# breadBUG_v1.net
KiCad netlist of a schematic drawn in EAGLE
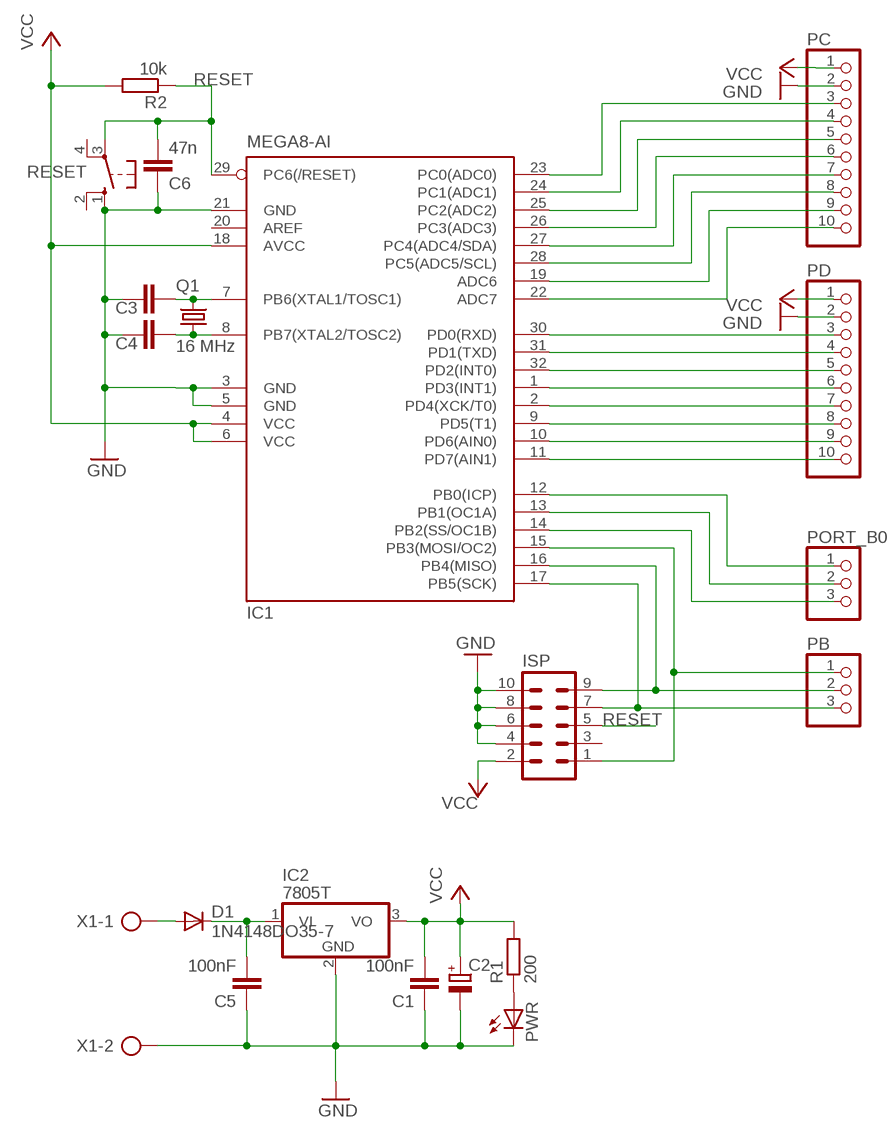
[diagram p0: schematic, sheet 1]

(export (version "E")
  (design (tool "Eeschema 10.0.6"))
  (components
    (comp (ref "C1")
      (value "100nF")
      (footprint "eagle-import:C2.5-2")
      (libsource (lib "eagle-import") (part "C2.5/2"))
    )
    (comp (ref "C2")
      (value "CPOL-EUE2.5-6")
      (footprint "eagle-import:E2,5-6")
      (libsource (lib "eagle-import") (part "CPOL-EUE2.5-6"))
    )
    (comp (ref "C3")
      (value "C-EU025-025X050")
      (footprint "eagle-import:C025-025X050")
      (libsource (lib "eagle-import") (part "C-EU025-025X050"))
    )
    (comp (ref "C4")
      (value "C-EU025-025X050")
      (footprint "eagle-import:C025-025X050")
      (libsource (lib "eagle-import") (part "C-EU025-025X050"))
    )
    (comp (ref "C5")
      (value "100nF")
      (footprint "eagle-import:C2.5-2")
      (libsource (lib "eagle-import") (part "C2.5/2"))
    )
    (comp (ref "C6")
      (value "47n")
      (footprint "eagle-import:C025-025X050")
      (libsource (lib "eagle-import") (part "C-EU025-025X050"))
    )
    (comp (ref "D1")
      (value "1N4148DO35-7")
      (footprint "eagle-import:DO35-7")
      (libsource (lib "eagle-import") (part "1N4148DO35-7"))
    )
    (comp (ref "IC1")
      (value "MEGA8-AI")
      (footprint "eagle-import:TQFP32-08")
      (fields (field (name "MPN") "ATMEGA8-16AU"))
      (libsource (lib "eagle-import") (part "MEGA8-AI"))
    )
    (comp (ref "IC2")
      (value "7805T")
      (footprint "eagle-import:TO220H")
      (libsource (lib "eagle-import") (part "78T05"))
    )
    (comp (ref "ISP")
      (value "MA05-2")
      (footprint "eagle-import:MA05-2")
      (libsource (lib "eagle-import") (part "MA05-2"))
    )
    (comp (ref "PB")
      (value "PINHD-1X3")
      (footprint "eagle-import:1X03")
      (libsource (lib "eagle-import") (part "PINHD-1X3"))
    )
    (comp (ref "PC")
      (value "PINHD-1X10")
      (footprint "eagle-import:1X10")
      (libsource (lib "eagle-import") (part "PINHD-1X10"))
    )
    (comp (ref "PD")
      (value "PINHD-1X10")
      (footprint "eagle-import:1X10")
      (libsource (lib "eagle-import") (part "PINHD-1X10"))
    )
    (comp (ref "PORT_B0")
      (value "PINHD-1X3")
      (footprint "eagle-import:1X03")
      (libsource (lib "eagle-import") (part "PINHD-1X3"))
    )
    (comp (ref "PWR")
      (value "LED3MM")
      (footprint "eagle-import:LED3MM")
      (libsource (lib "eagle-import") (part "LED3MM"))
    )
    (comp (ref "Q1")
      (value "16 MHz")
      (footprint "eagle-import:HC49U-V")
      (libsource (lib "eagle-import") (part "CRYSTALHC49U-V"))
    )
    (comp (ref "R1")
      (value "200")
      (footprint "eagle-import:0204V")
      (libsource (lib "eagle-import") (part "R-EU_0204/2V"))
    )
    (comp (ref "R2")
      (value "10k")
      (footprint "eagle-import:0204V")
      (libsource (lib "eagle-import") (part "R-EU_0204/2V"))
    )
    (comp (ref "RESET")
      (value "10-XX")
      (footprint "eagle-import:B3F-10XX")
      (fields
        (field (name "MPN") "B3F-1000")
        (field (name "MPN_1") "B3F-1000")
        (field (name "OC_FARNELL") "176432")
        (field (name "OC_NEWARK") "36M3542")
      )
      (libsource (lib "eagle-import") (part "10-XX"))
    )
    (comp (ref "X1")
      (value "AK500/2")
      (footprint "eagle-import:AK500_2")
      (libsource (lib "eagle-import") (part "AK500/2"))
    )
  )
  (nets
    (net (code "1") (name "/RESET") (class "Default")
      (node (ref "C6") (pin "2") (pinfunction "2_2") (pintype "passive"))
      (node (ref "IC1") (pin "29") (pinfunction "PC6(/RESET)_29") (pintype "bidirectional"))
      (node (ref "ISP") (pin "5") (pinfunction "5_5") (pintype "passive"))
      (node (ref "R2") (pin "1") (pinfunction "1_1") (pintype "passive"))
      (node (ref "RESET") (pin "3") (pinfunction "P_3") (pintype "passive"))
    )
    (net (code "2") (name "GND") (class "Default")
      (node (ref "C1") (pin "1") (pinfunction "1_1") (pintype "passive"))
      (node (ref "C2") (pin "-") (pinfunction "-_-") (pintype "passive"))
      (node (ref "C3") (pin "1") (pinfunction "1_1") (pintype "passive"))
      (node (ref "C4") (pin "1") (pinfunction "1_1") (pintype "passive"))
      (node (ref "C5") (pin "1") (pinfunction "1_1") (pintype "passive"))
      (node (ref "C6") (pin "1") (pinfunction "1_1") (pintype "passive"))
      (node (ref "IC1") (pin "21") (pinfunction "GND_21") (pintype "power_in"))
      (node (ref "IC1") (pin "3") (pinfunction "GND_3") (pintype "power_in"))
      (node (ref "IC1") (pin "5") (pinfunction "GND_5") (pintype "power_in"))
      (node (ref "IC2") (pin "2") (pinfunction "GND_2") (pintype "passive"))
      (node (ref "ISP") (pin "10") (pinfunction "10_10") (pintype "passive"))
      (node (ref "ISP") (pin "4") (pinfunction "4_4") (pintype "passive"))
      (node (ref "ISP") (pin "6") (pinfunction "6_6") (pintype "passive"))
      (node (ref "ISP") (pin "8") (pinfunction "8_8") (pintype "passive"))
      (node (ref "PC") (pin "2") (pinfunction "2_2") (pintype "passive"))
      (node (ref "PD") (pin "2") (pinfunction "2_2") (pintype "passive"))
      (node (ref "PWR") (pin "K") (pinfunction "C_K") (pintype "passive"))
      (node (ref "RESET") (pin "1") (pinfunction "S_1") (pintype "passive"))
      (node (ref "X1") (pin "2") (pinfunction "KL_2") (pintype "passive"))
    )
    (net (code "3") (name "Net-(IC1-ADC6)") (class "Default")
      (node (ref "IC1") (pin "19") (pinfunction "ADC6_19") (pintype "bidirectional"))
      (node (ref "PC") (pin "9") (pinfunction "9_9") (pintype "passive"))
    )
    (net (code "4") (name "Net-(IC1-ADC7)") (class "Default")
      (node (ref "IC1") (pin "22") (pinfunction "ADC7_22") (pintype "bidirectional"))
      (node (ref "PC") (pin "10") (pinfunction "10_10") (pintype "passive"))
    )
    (net (code "5") (name "Net-(IC1-PB0(ICP))") (class "Default")
      (node (ref "IC1") (pin "12") (pinfunction "PB0(ICP)_12") (pintype "bidirectional"))
      (node (ref "PORT_B0") (pin "1") (pinfunction "1_1") (pintype "passive"))
    )
    (net (code "6") (name "Net-(IC1-PB1(OC1A))") (class "Default")
      (node (ref "IC1") (pin "13") (pinfunction "PB1(OC1A)_13") (pintype "bidirectional"))
      (node (ref "PORT_B0") (pin "2") (pinfunction "2_2") (pintype "passive"))
    )
    (net (code "7") (name "Net-(IC1-PB2(SS{slash}OC1B))") (class "Default")
      (node (ref "IC1") (pin "14") (pinfunction "PB2(SS/OC1B)_14") (pintype "bidirectional"))
      (node (ref "PORT_B0") (pin "3") (pinfunction "3_3") (pintype "passive"))
    )
    (net (code "8") (name "Net-(IC1-PB3(MOSI{slash}OC2))") (class "Default")
      (node (ref "IC1") (pin "15") (pinfunction "PB3(MOSI/OC2)_15") (pintype "bidirectional"))
      (node (ref "ISP") (pin "1") (pinfunction "1_1") (pintype "passive"))
      (node (ref "PB") (pin "1") (pinfunction "1_1") (pintype "passive"))
    )
    (net (code "9") (name "Net-(IC1-PB4(MISO))") (class "Default")
      (node (ref "IC1") (pin "16") (pinfunction "PB4(MISO)_16") (pintype "bidirectional"))
      (node (ref "ISP") (pin "9") (pinfunction "9_9") (pintype "passive"))
      (node (ref "PB") (pin "2") (pinfunction "2_2") (pintype "passive"))
    )
    (net (code "10") (name "Net-(IC1-PB5(SCK))") (class "Default")
      (node (ref "IC1") (pin "17") (pinfunction "PB5(SCK)_17") (pintype "bidirectional"))
      (node (ref "ISP") (pin "7") (pinfunction "7_7") (pintype "passive"))
      (node (ref "PB") (pin "3") (pinfunction "3_3") (pintype "passive"))
    )
    (net (code "11") (name "Net-(IC1-PB6(XTAL1{slash}TOSC1))") (class "Default")
      (node (ref "C3") (pin "2") (pinfunction "2_2") (pintype "passive"))
      (node (ref "IC1") (pin "7") (pinfunction "PB6(XTAL1/TOSC1)_7") (pintype "bidirectional"))
      (node (ref "Q1") (pin "2") (pinfunction "2_2") (pintype "passive"))
    )
    (net (code "12") (name "Net-(IC1-PB7(XTAL2{slash}TOSC2))") (class "Default")
      (node (ref "C4") (pin "2") (pinfunction "2_2") (pintype "passive"))
      (node (ref "IC1") (pin "8") (pinfunction "PB7(XTAL2/TOSC2)_8") (pintype "bidirectional"))
      (node (ref "Q1") (pin "1") (pinfunction "1_1") (pintype "passive"))
    )
    (net (code "13") (name "Net-(IC1-PC0(ADC0))") (class "Default")
      (node (ref "IC1") (pin "23") (pinfunction "PC0(ADC0)_23") (pintype "bidirectional"))
      (node (ref "PC") (pin "3") (pinfunction "3_3") (pintype "passive"))
    )
    (net (code "14") (name "Net-(IC1-PC1(ADC1))") (class "Default")
      (node (ref "IC1") (pin "24") (pinfunction "PC1(ADC1)_24") (pintype "bidirectional"))
      (node (ref "PC") (pin "4") (pinfunction "4_4") (pintype "passive"))
    )
    (net (code "15") (name "Net-(IC1-PC2(ADC2))") (class "Default")
      (node (ref "IC1") (pin "25") (pinfunction "PC2(ADC2)_25") (pintype "bidirectional"))
      (node (ref "PC") (pin "5") (pinfunction "5_5") (pintype "passive"))
    )
    (net (code "16") (name "Net-(IC1-PC3(ADC3))") (class "Default")
      (node (ref "IC1") (pin "26") (pinfunction "PC3(ADC3)_26") (pintype "bidirectional"))
      (node (ref "PC") (pin "6") (pinfunction "6_6") (pintype "passive"))
    )
    (net (code "17") (name "Net-(IC1-PC4(ADC4{slash}SDA))") (class "Default")
      (node (ref "IC1") (pin "27") (pinfunction "PC4(ADC4/SDA)_27") (pintype "bidirectional"))
      (node (ref "PC") (pin "7") (pinfunction "7_7") (pintype "passive"))
    )
    (net (code "18") (name "Net-(IC1-PC5(ADC5{slash}SCL))") (class "Default")
      (node (ref "IC1") (pin "28") (pinfunction "PC5(ADC5/SCL)_28") (pintype "bidirectional"))
      (node (ref "PC") (pin "8") (pinfunction "8_8") (pintype "passive"))
    )
    (net (code "19") (name "Net-(IC1-PD0(RXD))") (class "Default")
      (node (ref "IC1") (pin "30") (pinfunction "PD0(RXD)_30") (pintype "bidirectional"))
      (node (ref "PD") (pin "3") (pinfunction "3_3") (pintype "passive"))
    )
    (net (code "20") (name "Net-(IC1-PD1(TXD))") (class "Default")
      (node (ref "IC1") (pin "31") (pinfunction "PD1(TXD)_31") (pintype "bidirectional"))
      (node (ref "PD") (pin "4") (pinfunction "4_4") (pintype "passive"))
    )
    (net (code "21") (name "Net-(IC1-PD2(INT0))") (class "Default")
      (node (ref "IC1") (pin "32") (pinfunction "PD2(INT0)_32") (pintype "bidirectional"))
      (node (ref "PD") (pin "5") (pinfunction "5_5") (pintype "passive"))
    )
    (net (code "22") (name "Net-(IC1-PD3(INT1))") (class "Default")
      (node (ref "IC1") (pin "1") (pinfunction "PD3(INT1)_1") (pintype "bidirectional"))
      (node (ref "PD") (pin "6") (pinfunction "6_6") (pintype "passive"))
    )
    (net (code "23") (name "Net-(IC1-PD4(XCK{slash}T0))") (class "Default")
      (node (ref "IC1") (pin "2") (pinfunction "PD4(XCK/T0)_2") (pintype "bidirectional"))
      (node (ref "PD") (pin "7") (pinfunction "7_7") (pintype "passive"))
    )
    (net (code "24") (name "Net-(IC1-PD5(T1))") (class "Default")
      (node (ref "IC1") (pin "9") (pinfunction "PD5(T1)_9") (pintype "bidirectional"))
      (node (ref "PD") (pin "8") (pinfunction "8_8") (pintype "passive"))
    )
    (net (code "25") (name "Net-(IC1-PD6(AIN0))") (class "Default")
      (node (ref "IC1") (pin "10") (pinfunction "PD6(AIN0)_10") (pintype "bidirectional"))
      (node (ref "PD") (pin "9") (pinfunction "9_9") (pintype "passive"))
    )
    (net (code "26") (name "Net-(IC1-PD7(AIN1))") (class "Default")
      (node (ref "IC1") (pin "11") (pinfunction "PD7(AIN1)_11") (pintype "bidirectional"))
      (node (ref "PD") (pin "10") (pinfunction "10_10") (pintype "passive"))
    )
    (net (code "27") (name "Net-(IC2-VI)") (class "Default")
      (node (ref "C5") (pin "2") (pinfunction "2_2") (pintype "passive"))
      (node (ref "D1") (pin "C") (pinfunction "C_C") (pintype "passive"))
      (node (ref "IC2") (pin "1") (pinfunction "VI_1") (pintype "input"))
    )
    (net (code "28") (name "Net-(PWR-PadA)") (class "Default")
      (node (ref "PWR") (pin "A") (pinfunction "A_A") (pintype "passive"))
      (node (ref "R1") (pin "1") (pinfunction "1_1") (pintype "passive"))
    )
    (net (code "29") (name "Net-(X1A-KL)") (class "Default")
      (node (ref "D1") (pin "A") (pinfunction "A_A") (pintype "passive"))
      (node (ref "X1") (pin "1") (pinfunction "KL_1") (pintype "passive"))
    )
    (net (code "30") (name "VCC") (class "Default")
      (node (ref "C1") (pin "2") (pinfunction "2_2") (pintype "passive"))
      (node (ref "C2") (pin "+") (pinfunction "+_+") (pintype "passive"))
      (node (ref "IC1") (pin "18") (pinfunction "AVCC_18") (pintype "power_in"))
      (node (ref "IC1") (pin "4") (pinfunction "VCC_4") (pintype "power_in"))
      (node (ref "IC1") (pin "6") (pinfunction "VCC_6") (pintype "power_in"))
      (node (ref "IC2") (pin "3") (pinfunction "VO_3") (pintype "passive"))
      (node (ref "ISP") (pin "2") (pinfunction "2_2") (pintype "passive"))
      (node (ref "PC") (pin "1") (pinfunction "1_1") (pintype "passive"))
      (node (ref "PD") (pin "1") (pinfunction "1_1") (pintype "passive"))
      (node (ref "R1") (pin "2") (pinfunction "2_2") (pintype "passive"))
      (node (ref "R2") (pin "2") (pinfunction "2_2") (pintype "passive"))
    )
    (net (code "31") (name "unconnected-(IC1-AREF-Pad20)") (class "Default")
      (node (ref "IC1") (pin "20") (pinfunction "AREF_20") (pintype "passive"))
    )
    (net (code "32") (name "unconnected-(ISP-Pad3)") (class "Default")
      (node (ref "ISP") (pin "3") (pinfunction "3_3") (pintype "passive"))
    )
    (net (code "33") (name "unconnected-(RESET-P1-Pad4)") (class "Default")
      (node (ref "RESET") (pin "4") (pinfunction "P1_4") (pintype "passive"))
    )
    (net (code "34") (name "unconnected-(RESET-S1-Pad2)") (class "Default")
      (node (ref "RESET") (pin "2") (pinfunction "S1_2") (pintype "passive"))
    )
  )
)
